# TermWylPomp1_supp.net
KiCad netlist of a schematic drawn in Altium Designer
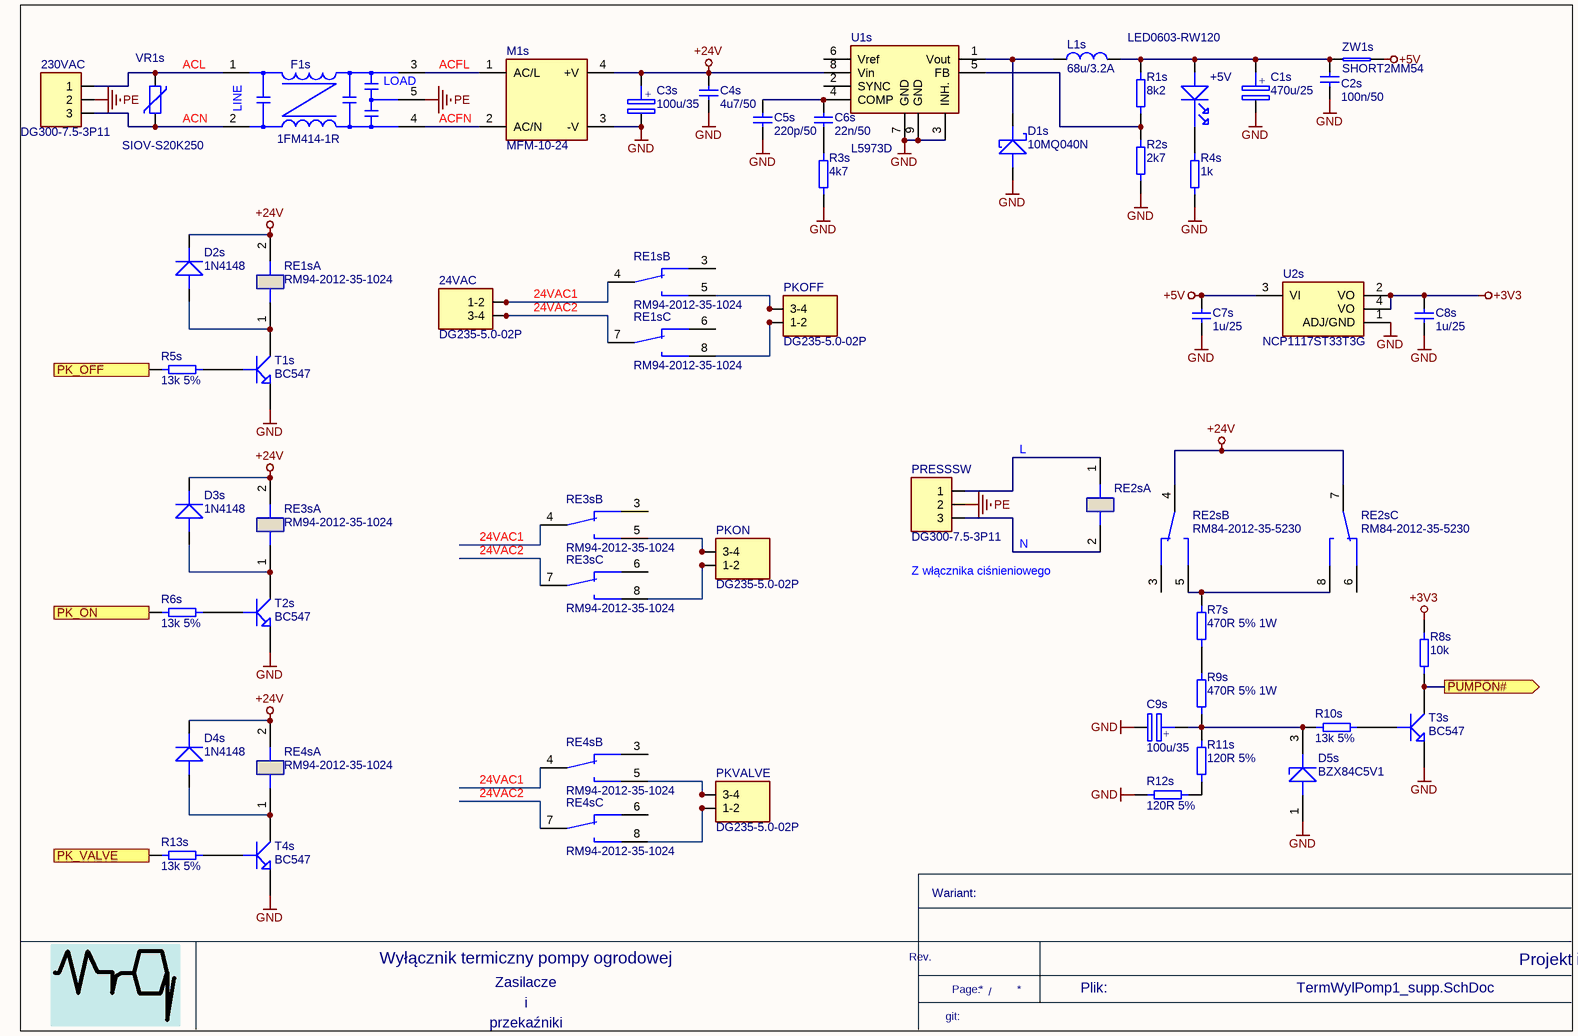
[diagram p0: TermWylPomp1_supp.SchDoc]

(export (version "E")
  (design (tool "Eeschema 10.0.6"))
  (components
    (comp (ref "+5V") (value "LED0603-RW120") (footprint "D0603") (libsource (lib "PartsMySQL") (part "LED")))
    (comp (ref "24VAC")
      (value "DG235-5.0-02P")
      (footprint "DG235-5.0-02P")
      (libsource (lib "") (part "DG235-5.0-02P_1"))
    )
    (comp (ref "230VAC")
      (value "DG300-7.5-3P11")
      (footprint "DG300-7.5-3P11")
      (libsource (lib "PartsMySQL") (part "HEADER3"))
    )
    (comp (ref "C1s") (value "470u/25") (footprint "CE2040") (libsource (lib "PartsMySQL") (part "CEL")))
    (comp (ref "C2s") (value "100n/50") (footprint "0805") (libsource (lib "PartsMySQL") (part "C")))
    (comp (ref "C3s") (value "100u/35") (footprint "CE1028") (libsource (lib "PartsMySQL") (part "CEL")))
    (comp (ref "C4s") (value "4u7/50") (footprint "1210") (libsource (lib "PartsMySQL") (part "C")))
    (comp (ref "C5s") (value "220p/50") (footprint "0603-IPC") (libsource (lib "PartsMySQL") (part "C")))
    (comp (ref "C6s") (value "22n/50") (footprint "0603-IPC") (libsource (lib "PartsMySQL") (part "C")))
    (comp (ref "C7s") (value "1u/25") (footprint "0805") (libsource (lib "PartsMySQL") (part "C")))
    (comp (ref "C8s") (value "1u/25") (footprint "0805") (libsource (lib "PartsMySQL") (part "C")))
    (comp (ref "C9s") (value "100u/35") (footprint "CE1028") (libsource (lib "PartsMySQL") (part "CEL")))
    (comp (ref "D1s")
      (value "10MQ040N")
      (footprint "SMA")
      (libsource (lib "PartsMySQL") (part "DIODE_SCHOTTKY"))
    )
    (comp (ref "D2s") (value "1N4148") (footprint "CE02") (libsource (lib "PartsMySQL") (part "DIODE")))
    (comp (ref "D3s") (value "1N4148") (footprint "CE02") (libsource (lib "PartsMySQL") (part "DIODE")))
    (comp (ref "D4s") (value "1N4148") (footprint "CE02") (libsource (lib "PartsMySQL") (part "DIODE")))
    (comp (ref "D5s")
      (value "BZX84C5V1")
      (footprint "SOT23-3")
      (libsource (lib "PartsMySQL") (part "ZENER_SOT23_13"))
    )
    (comp (ref "F1s") (value "1FM414-1R") (footprint "1FM414") (libsource (lib "PartsMySQL") (part "1FM414")))
    (comp (ref "L1s")
      (value "68u/3.2A")
      (footprint "SRR1208")
      (libsource (lib "PartsMySQL") (part "INDUCTOR"))
    )
    (comp (ref "M1s")
      (value "MFM-10-24")
      (footprint "MFM-10-24")
      (libsource (lib "PartsMySQL") (part "PM-10-5"))
    )
    (comp (ref "PKOFF")
      (value "DG235-5.0-02P")
      (footprint "DG235-5.0-02P")
      (libsource (lib "PartsMySQL") (part "DG235-5.0-02P"))
    )
    (comp (ref "PKON")
      (value "DG235-5.0-02P")
      (footprint "DG235-5.0-02P")
      (libsource (lib "PartsMySQL") (part "DG235-5.0-02P"))
    )
    (comp (ref "PKVALVE")
      (value "DG235-5.0-02P")
      (footprint "DG235-5.0-02P")
      (libsource (lib "PartsMySQL") (part "DG235-5.0-02P"))
    )
    (comp (ref "PRESSSW")
      (value "DG300-7.5-3P11")
      (footprint "DG300-7.5-3P11")
      (libsource (lib "PartsMySQL") (part "HEADER3"))
    )
    (comp (ref "R1s") (value "8k2") (footprint "0805R") (libsource (lib "PartsMySQL") (part "R")))
    (comp (ref "R2s") (value "2k7") (footprint "0805R") (libsource (lib "PartsMySQL") (part "R")))
    (comp (ref "R3s") (value "4k7") (footprint "0603R") (libsource (lib "PartsMySQL") (part "R")))
    (comp (ref "R4s") (value "1k") (footprint "0805R") (libsource (lib "PartsMySQL") (part "R")))
    (comp (ref "R5s") (value "13k 5%") (footprint "R402510") (libsource (lib "PartsMySQL") (part "R")))
    (comp (ref "R6s") (value "13k 5%") (footprint "R402510") (libsource (lib "PartsMySQL") (part "R")))
    (comp (ref "R7s") (value "470R 5% 1W") (footprint "R705226") (libsource (lib "PartsMySQL") (part "R")))
    (comp (ref "R8s") (value "10k") (footprint "R402510") (libsource (lib "PartsMySQL") (part "R")))
    (comp (ref "R9s") (value "470R 5% 1W") (footprint "R705226") (libsource (lib "PartsMySQL") (part "R")))
    (comp (ref "R10s") (value "13k 5%") (footprint "R402510") (libsource (lib "PartsMySQL") (part "R")))
    (comp (ref "R11s") (value "120R 5%") (footprint "R402510") (libsource (lib "PartsMySQL") (part "R")))
    (comp (ref "R12s") (value "120R 5%") (footprint "R402510") (libsource (lib "PartsMySQL") (part "R")))
    (comp (ref "R13s") (value "13k 5%") (footprint "R402510") (libsource (lib "PartsMySQL") (part "R")))
    (comp (ref "RE1s")
      (value "RM94-2012-35-1024")
      (footprint "RM84-P")
      (libsource (lib "PartsMySQL") (part "RM84-P"))
    )
    (comp (ref "RE2s")
      (value "RM84-2012-35-5230")
      (footprint "RM84-P")
      (libsource (lib "") (part "RM84-P_1"))
    )
    (comp (ref "RE3s")
      (value "RM94-2012-35-1024")
      (footprint "RM84-P")
      (libsource (lib "") (part "RM84-P_2"))
    )
    (comp (ref "RE4s")
      (value "RM94-2012-35-1024")
      (footprint "RM84-P")
      (libsource (lib "") (part "RM84-P_2"))
    )
    (comp (ref "T1s") (value "BC547") (footprint "CE35V4") (libsource (lib "PartsMySQL") (part "NPN_CE35V4")))
    (comp (ref "T2s") (value "BC547") (footprint "CE35V4") (libsource (lib "PartsMySQL") (part "NPN_CE35V4")))
    (comp (ref "T3s") (value "BC547") (footprint "CE35V4") (libsource (lib "PartsMySQL") (part "NPN_CE35V4")))
    (comp (ref "T4s") (value "BC547") (footprint "CE35V4") (libsource (lib "PartsMySQL") (part "NPN_CE35V4")))
    (comp (ref "U1s") (value "L5973D") (footprint "HSOP8") (libsource (lib "PartsMySQL") (part "L5973")))
    (comp (ref "U2s")
      (value "NCP1117ST33T3G")
      (footprint "SOT-223")
      (libsource (lib "PartsMySQL") (part "LM1117IMP"))
    )
    (comp (ref "VR1s")
      (value "SIOV-S20K250")
      (footprint "SIOV-S20K275")
      (libsource (lib "PartsMySQL") (part "VARISTOR"))
    )
    (comp (ref "ZW1s")
      (value "SHORT2MM54")
      (footprint "SHUNT_2MM54")
      (libsource (lib "PartsMySQL") (part "SHORT"))
    )
  )
  (nets
    (net (code "1") (name "+3V3") (class "Default")
      (node (ref "C8s") (pin "1") (pinfunction "1_1") (pintype "passive"))
      (node (ref "R8s") (pin "1") (pinfunction "1_1") (pintype "passive"))
      (node (ref "U2s") (pin "2") (pinfunction "VO_2") (pintype "passive"))
      (node (ref "U2s") (pin "4") (pinfunction "VO_4") (pintype "passive"))
    )
    (net (code "2") (name "+5V") (class "Default")
      (node (ref "C7s") (pin "1") (pinfunction "1_1") (pintype "passive"))
      (node (ref "U2s") (pin "3") (pinfunction "VI_3") (pintype "passive"))
      (node (ref "ZW1s") (pin "2") (pinfunction "2_2") (pintype "passive"))
    )
    (net (code "3") (name "+24V") (class "Default")
      (node (ref "C3s") (pin "2") (pinfunction "2_2") (pintype "passive"))
      (node (ref "C4s") (pin "1") (pinfunction "1_1") (pintype "passive"))
      (node (ref "D2s") (pin "CATH") (pinfunction "CATH_CATH") (pintype "passive"))
      (node (ref "D3s") (pin "CATH") (pinfunction "CATH_CATH") (pintype "passive"))
      (node (ref "D4s") (pin "CATH") (pinfunction "CATH_CATH") (pintype "passive"))
      (node (ref "M1s") (pin "4") (pinfunction "+V_4") (pintype "passive"))
      (node (ref "RE1s") (pin "2") (pinfunction "A2_2") (pintype "passive"))
      (node (ref "RE2s") (pin "4") (pinfunction "21_4") (pintype "passive"))
      (node (ref "RE2s") (pin "7") (pinfunction "11_7") (pintype "passive"))
      (node (ref "RE3s") (pin "2") (pinfunction "A2_2") (pintype "passive"))
      (node (ref "RE4s") (pin "2") (pinfunction "A2_2") (pintype "passive"))
      (node (ref "U1s") (pin "8") (pinfunction "Vin_8") (pintype "passive"))
    )
    (net (code "4") (name "/24VAC1") (class "Default")
      (node (ref "24VAC") (pin "1") (pinfunction "1-2_1") (pintype "passive"))
      (node (ref "24VAC") (pin "2") (pinfunction "2_2") (pintype "passive"))
      (node (ref "RE1s") (pin "4") (pinfunction "21_4") (pintype "passive"))
      (node (ref "RE3s") (pin "4") (pinfunction "21_4") (pintype "passive"))
      (node (ref "RE4s") (pin "4") (pinfunction "21_4") (pintype "passive"))
    )
    (net (code "5") (name "/24VAC2") (class "Default")
      (node (ref "24VAC") (pin "3") (pinfunction "3-4_3") (pintype "passive"))
      (node (ref "24VAC") (pin "4") (pinfunction "4_4") (pintype "passive"))
      (node (ref "RE1s") (pin "7") (pinfunction "11_7") (pintype "passive"))
      (node (ref "RE3s") (pin "7") (pinfunction "11_7") (pintype "passive"))
      (node (ref "RE4s") (pin "7") (pinfunction "11_7") (pintype "passive"))
    )
    (net (code "6") (name "/ACFL") (class "Default")
      (node (ref "F1s") (pin "3") (pinfunction "OUT2_3") (pintype "passive"))
      (node (ref "M1s") (pin "1") (pinfunction "AC/L_1") (pintype "passive"))
    )
    (net (code "7") (name "/ACFN") (class "Default")
      (node (ref "F1s") (pin "4") (pinfunction "OUT1_4") (pintype "passive"))
      (node (ref "M1s") (pin "2") (pinfunction "AC/N_2") (pintype "passive"))
    )
    (net (code "8") (name "/ACL") (class "Default")
      (node (ref "230VAC") (pin "1") (pinfunction "1_1") (pintype "passive"))
      (node (ref "F1s") (pin "1") (pinfunction "IN1_1") (pintype "passive"))
      (node (ref "VR1s") (pin "1") (pinfunction "1_1") (pintype "passive"))
    )
    (net (code "9") (name "/ACN") (class "Default")
      (node (ref "230VAC") (pin "3") (pinfunction "3_3") (pintype "passive"))
      (node (ref "F1s") (pin "2") (pinfunction "IN2_2") (pintype "passive"))
      (node (ref "VR1s") (pin "2") (pinfunction "2_2") (pintype "passive"))
    )
    (net (code "10") (name "/PK_OFF") (class "Default")
      (node (ref "R5s") (pin "1") (pinfunction "1_1") (pintype "passive"))
    )
    (net (code "11") (name "/PK_ON") (class "Default")
      (node (ref "R6s") (pin "1") (pinfunction "1_1") (pintype "passive"))
    )
    (net (code "12") (name "/PK_VALVE") (class "Default")
      (node (ref "R13s") (pin "1") (pinfunction "1_1") (pintype "passive"))
    )
    (net (code "13") (name "/PUMPON#") (class "Default")
      (node (ref "R8s") (pin "2") (pinfunction "2_2") (pintype "passive"))
      (node (ref "T3s") (pin "COLL") (pinfunction "COLL_COLL") (pintype "passive"))
    )
    (net (code "14") (name "GND") (class "Default")
      (node (ref "C1s") (pin "1") (pinfunction "1_1") (pintype "passive"))
      (node (ref "C2s") (pin "2") (pinfunction "2_2") (pintype "passive"))
      (node (ref "C3s") (pin "1") (pinfunction "1_1") (pintype "passive"))
      (node (ref "C4s") (pin "2") (pinfunction "2_2") (pintype "passive"))
      (node (ref "C5s") (pin "2") (pinfunction "2_2") (pintype "passive"))
      (node (ref "C7s") (pin "2") (pinfunction "2_2") (pintype "passive"))
      (node (ref "C8s") (pin "2") (pinfunction "2_2") (pintype "passive"))
      (node (ref "C9s") (pin "1") (pinfunction "1_1") (pintype "passive"))
      (node (ref "D1s") (pin "2") (pinfunction "ANOD_2") (pintype "passive"))
      (node (ref "D5s") (pin "1") (pinfunction "1_1") (pintype "passive"))
      (node (ref "M1s") (pin "3") (pinfunction "-V_3") (pintype "passive"))
      (node (ref "R12s") (pin "2") (pinfunction "2_2") (pintype "passive"))
      (node (ref "R2s") (pin "2") (pinfunction "2_2") (pintype "passive"))
      (node (ref "R3s") (pin "2") (pinfunction "2_2") (pintype "passive"))
      (node (ref "R4s") (pin "2") (pinfunction "2_2") (pintype "passive"))
      (node (ref "T1s") (pin "EMIT") (pinfunction "EMIT_EMIT") (pintype "passive"))
      (node (ref "T2s") (pin "EMIT") (pinfunction "EMIT_EMIT") (pintype "passive"))
      (node (ref "T3s") (pin "EMIT") (pinfunction "EMIT_EMIT") (pintype "passive"))
      (node (ref "T4s") (pin "EMIT") (pinfunction "EMIT_EMIT") (pintype "passive"))
      (node (ref "U1s") (pin "3") (pinfunction "INH._3") (pintype "passive"))
      (node (ref "U1s") (pin "7") (pinfunction "GND_7") (pintype "passive"))
      (node (ref "U1s") (pin "9") (pinfunction "GND_9") (pintype "passive"))
      (node (ref "U2s") (pin "1") (pinfunction "ADJ/GND_1") (pintype "passive"))
    )
    (net (code "15") (name "Net-(+5V-PadANOD)") (class "Default")
      (node (ref "+5V") (pin "ANOD") (pinfunction "ANOD_ANOD") (pintype "passive"))
      (node (ref "C1s") (pin "2") (pinfunction "2_2") (pintype "passive"))
      (node (ref "C2s") (pin "1") (pinfunction "1_1") (pintype "passive"))
      (node (ref "L1s") (pin "2") (pinfunction "2_2") (pintype "passive"))
      (node (ref "R1s") (pin "1") (pinfunction "1_1") (pintype "passive"))
      (node (ref "ZW1s") (pin "1") (pinfunction "1_1") (pintype "passive"))
    )
    (net (code "16") (name "Net-(+5V-PadCATH)") (class "Default")
      (node (ref "+5V") (pin "CATH") (pinfunction "CATH_CATH") (pintype "passive"))
      (node (ref "R4s") (pin "1") (pinfunction "1_1") (pintype "passive"))
    )
    (net (code "17") (name "Net-(C6s-Pad2)") (class "Default")
      (node (ref "C6s") (pin "2") (pinfunction "2_2") (pintype "passive"))
      (node (ref "R3s") (pin "1") (pinfunction "1_1") (pintype "passive"))
    )
    (net (code "18") (name "Net-(C9s-Pad2)") (class "Default")
      (node (ref "C9s") (pin "2") (pinfunction "2_2") (pintype "passive"))
      (node (ref "D5s") (pin "3") (pinfunction "3_3") (pintype "passive"))
      (node (ref "R10s") (pin "1") (pinfunction "1_1") (pintype "passive"))
      (node (ref "R11s") (pin "1") (pinfunction "1_1") (pintype "passive"))
      (node (ref "R9s") (pin "2") (pinfunction "2_2") (pintype "passive"))
    )
    (net (code "19") (name "Net-(D1s-CATH)") (class "Default")
      (node (ref "D1s") (pin "1") (pinfunction "CATH_1") (pintype "passive"))
      (node (ref "L1s") (pin "1") (pinfunction "1_1") (pintype "passive"))
      (node (ref "U1s") (pin "1") (pinfunction "Vout_1") (pintype "passive"))
    )
    (net (code "20") (name "Net-(PKOFF-1-2)") (class "Default")
      (node (ref "PKOFF") (pin "1") (pinfunction "1-2_1") (pintype "passive"))
      (node (ref "PKOFF") (pin "2") (pinfunction "2_2") (pintype "passive"))
      (node (ref "RE1s") (pin "8") (pinfunction "14_8") (pintype "passive"))
    )
    (net (code "21") (name "Net-(PKOFF-3-4)") (class "Default")
      (node (ref "PKOFF") (pin "3") (pinfunction "3-4_3") (pintype "passive"))
      (node (ref "PKOFF") (pin "4") (pinfunction "4_4") (pintype "passive"))
      (node (ref "RE1s") (pin "5") (pinfunction "24_5") (pintype "passive"))
    )
    (net (code "22") (name "Net-(PKON-1-2)") (class "Default")
      (node (ref "PKON") (pin "1") (pinfunction "1-2_1") (pintype "passive"))
      (node (ref "PKON") (pin "2") (pinfunction "2_2") (pintype "passive"))
      (node (ref "RE3s") (pin "8") (pinfunction "14_8") (pintype "passive"))
    )
    (net (code "23") (name "Net-(PKON-3-4)") (class "Default")
      (node (ref "PKON") (pin "3") (pinfunction "3-4_3") (pintype "passive"))
      (node (ref "PKON") (pin "4") (pinfunction "4_4") (pintype "passive"))
      (node (ref "RE3s") (pin "5") (pinfunction "24_5") (pintype "passive"))
    )
    (net (code "24") (name "Net-(PKVALVE-1-2)") (class "Default")
      (node (ref "PKVALVE") (pin "1") (pinfunction "1-2_1") (pintype "passive"))
      (node (ref "PKVALVE") (pin "2") (pinfunction "2_2") (pintype "passive"))
      (node (ref "RE4s") (pin "8") (pinfunction "14_8") (pintype "passive"))
    )
    (net (code "25") (name "Net-(PKVALVE-3-4)") (class "Default")
      (node (ref "PKVALVE") (pin "3") (pinfunction "3-4_3") (pintype "passive"))
      (node (ref "PKVALVE") (pin "4") (pinfunction "4_4") (pintype "passive"))
      (node (ref "RE4s") (pin "5") (pinfunction "24_5") (pintype "passive"))
    )
    (net (code "26") (name "Net-(R5s-Pad2)") (class "Default")
      (node (ref "R5s") (pin "2") (pinfunction "2_2") (pintype "passive"))
      (node (ref "T1s") (pin "BASE") (pinfunction "BASE_BASE") (pintype "passive"))
    )
    (net (code "27") (name "Net-(R6s-Pad2)") (class "Default")
      (node (ref "R6s") (pin "2") (pinfunction "2_2") (pintype "passive"))
      (node (ref "T2s") (pin "BASE") (pinfunction "BASE_BASE") (pintype "passive"))
    )
    (net (code "28") (name "Net-(R7s-Pad2)") (class "Default")
      (node (ref "R7s") (pin "2") (pinfunction "2_2") (pintype "passive"))
      (node (ref "R9s") (pin "1") (pinfunction "1_1") (pintype "passive"))
    )
    (net (code "29") (name "Net-(R10s-Pad2)") (class "Default")
      (node (ref "R10s") (pin "2") (pinfunction "2_2") (pintype "passive"))
      (node (ref "T3s") (pin "BASE") (pinfunction "BASE_BASE") (pintype "passive"))
    )
    (net (code "30") (name "Net-(R11s-Pad2)") (class "Default")
      (node (ref "R11s") (pin "2") (pinfunction "2_2") (pintype "passive"))
      (node (ref "R12s") (pin "1") (pinfunction "1_1") (pintype "passive"))
    )
    (net (code "31") (name "Net-(R13s-Pad2)") (class "Default")
      (node (ref "R13s") (pin "2") (pinfunction "2_2") (pintype "passive"))
      (node (ref "T4s") (pin "BASE") (pinfunction "BASE_BASE") (pintype "passive"))
    )
    (net (code "32") (name "Net-(RE1sA-A1)") (class "Default")
      (node (ref "D2s") (pin "ANOD") (pinfunction "ANOD_ANOD") (pintype "passive"))
      (node (ref "RE1s") (pin "1") (pinfunction "A1_1") (pintype "passive"))
      (node (ref "T1s") (pin "COLL") (pinfunction "COLL_COLL") (pintype "passive"))
    )
    (net (code "33") (name "Net-(RE2sA-A1)") (class "Default")
      (node (ref "PRESSSW") (pin "1") (pinfunction "1_1") (pintype "passive"))
      (node (ref "RE2s") (pin "1") (pinfunction "A1_1") (pintype "passive"))
    )
    (net (code "34") (name "Net-(RE2sA-A2)") (class "Default")
      (node (ref "PRESSSW") (pin "3") (pinfunction "3_3") (pintype "passive"))
      (node (ref "RE2s") (pin "2") (pinfunction "A2_2") (pintype "passive"))
    )
    (net (code "35") (name "Net-(RE2sB-24)") (class "Default")
      (node (ref "R7s") (pin "1") (pinfunction "1_1") (pintype "passive"))
      (node (ref "RE2s") (pin "5") (pinfunction "24_5") (pintype "passive"))
      (node (ref "RE2s") (pin "8") (pinfunction "14_8") (pintype "passive"))
    )
    (net (code "36") (name "Net-(RE3sA-A1)") (class "Default")
      (node (ref "D3s") (pin "ANOD") (pinfunction "ANOD_ANOD") (pintype "passive"))
      (node (ref "RE3s") (pin "1") (pinfunction "A1_1") (pintype "passive"))
      (node (ref "T2s") (pin "COLL") (pinfunction "COLL_COLL") (pintype "passive"))
    )
    (net (code "37") (name "Net-(RE4sA-A1)") (class "Default")
      (node (ref "D4s") (pin "ANOD") (pinfunction "ANOD_ANOD") (pintype "passive"))
      (node (ref "RE4s") (pin "1") (pinfunction "A1_1") (pintype "passive"))
      (node (ref "T4s") (pin "COLL") (pinfunction "COLL_COLL") (pintype "passive"))
    )
    (net (code "38") (name "Net-(U1s-COMP)") (class "Default")
      (node (ref "C5s") (pin "1") (pinfunction "1_1") (pintype "passive"))
      (node (ref "C6s") (pin "1") (pinfunction "1_1") (pintype "passive"))
      (node (ref "U1s") (pin "4") (pinfunction "COMP_4") (pintype "passive"))
    )
    (net (code "39") (name "Net-(U1s-FB)") (class "Default")
      (node (ref "R1s") (pin "2") (pinfunction "2_2") (pintype "passive"))
      (node (ref "R2s") (pin "1") (pinfunction "1_1") (pintype "passive"))
      (node (ref "U1s") (pin "5") (pinfunction "FB_5") (pintype "passive"))
    )
    (net (code "40") (name "PE") (class "Default")
      (node (ref "230VAC") (pin "2") (pinfunction "2_2") (pintype "passive"))
      (node (ref "F1s") (pin "5") (pinfunction "5_5") (pintype "passive"))
      (node (ref "PRESSSW") (pin "2") (pinfunction "2_2") (pintype "passive"))
    )
    (net (code "41") (name "unconnected-(RE1sB-22-Pad3)") (class "Default")
      (node (ref "RE1s") (pin "3") (pinfunction "22_3") (pintype "passive"))
    )
    (net (code "42") (name "unconnected-(RE1sC-12-Pad6)") (class "Default")
      (node (ref "RE1s") (pin "6") (pinfunction "12_6") (pintype "passive"))
    )
    (net (code "43") (name "unconnected-(RE2sB-22-Pad3)") (class "Default")
      (node (ref "RE2s") (pin "3") (pinfunction "22_3") (pintype "passive"))
    )
    (net (code "44") (name "unconnected-(RE2sC-12-Pad6)") (class "Default")
      (node (ref "RE2s") (pin "6") (pinfunction "12_6") (pintype "passive"))
    )
    (net (code "45") (name "unconnected-(RE3sB-22-Pad3)") (class "Default")
      (node (ref "RE3s") (pin "3") (pinfunction "22_3") (pintype "passive"))
    )
    (net (code "46") (name "unconnected-(RE3sC-12-Pad6)") (class "Default")
      (node (ref "RE3s") (pin "6") (pinfunction "12_6") (pintype "passive"))
    )
    (net (code "47") (name "unconnected-(RE4sB-22-Pad3)") (class "Default")
      (node (ref "RE4s") (pin "3") (pinfunction "22_3") (pintype "passive"))
    )
    (net (code "48") (name "unconnected-(RE4sC-12-Pad6)") (class "Default")
      (node (ref "RE4s") (pin "6") (pinfunction "12_6") (pintype "passive"))
    )
    (net (code "49") (name "unconnected-(U1s-SYNC-Pad2)") (class "Default")
      (node (ref "U1s") (pin "2") (pinfunction "SYNC_2") (pintype "passive"))
    )
    (net (code "50") (name "unconnected-(U1s-Vref-Pad6)") (class "Default")
      (node (ref "U1s") (pin "6") (pinfunction "Vref_6") (pintype "passive"))
    )
  )
)
